# source_eagle.net
KiCad netlist of a schematic drawn in EAGLE
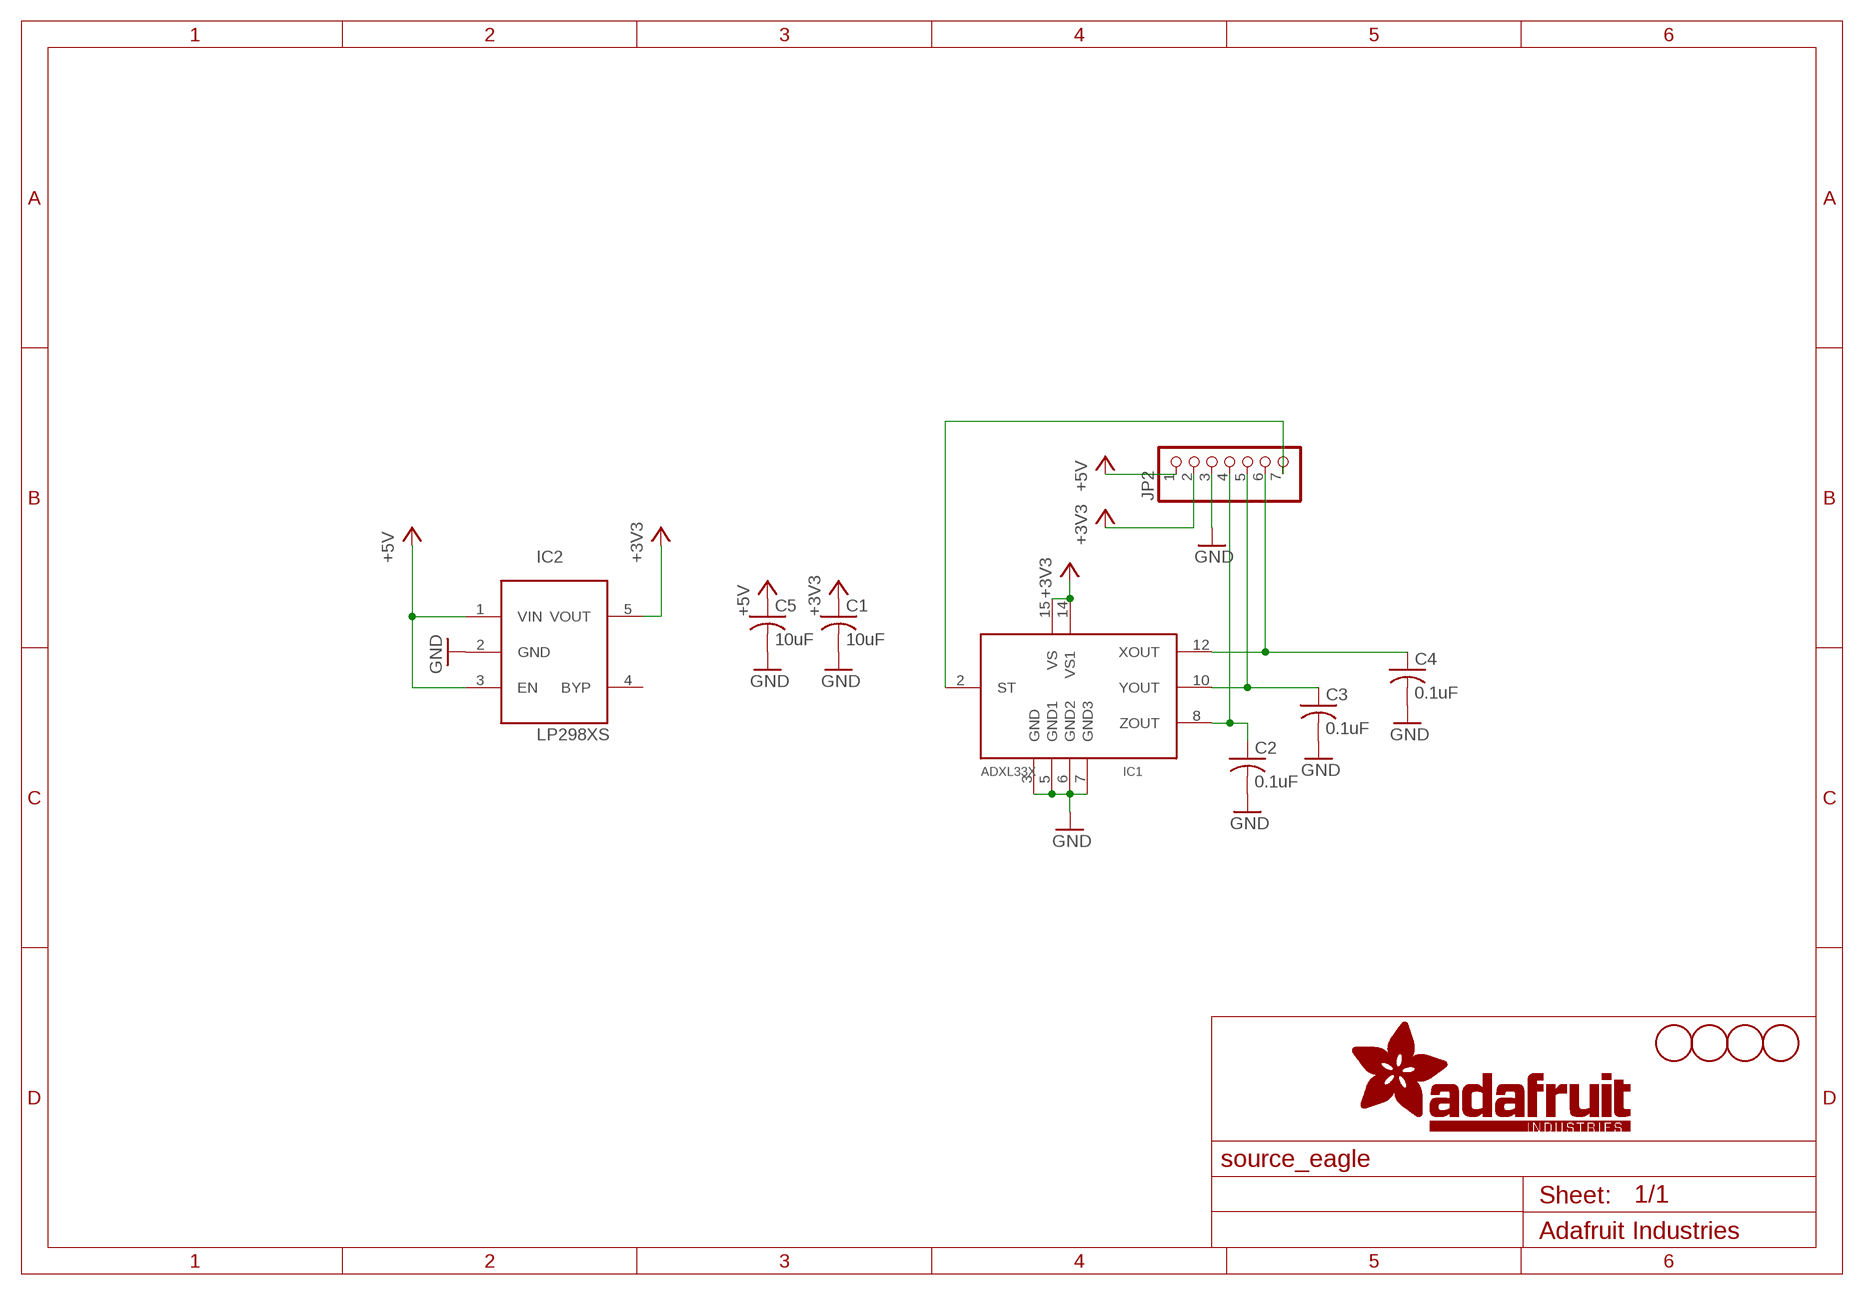
[diagram p0: schematic, sheet 1]

(export (version "E")
  (design (tool "Eeschema 10.0.6"))
  (components
    (comp (ref "C1")
      (value "10uF")
      (footprint "eagle-import:C0805K")
      (libsource (lib "eagle-import") (part "C-USC0805K"))
    )
    (comp (ref "C2")
      (value "0.1uF")
      (footprint "eagle-import:C0805K")
      (libsource (lib "eagle-import") (part "C-USC0805K"))
    )
    (comp (ref "C3")
      (value "0.1uF")
      (footprint "eagle-import:C0805K")
      (libsource (lib "eagle-import") (part "C-USC0805K"))
    )
    (comp (ref "C4")
      (value "0.1uF")
      (footprint "eagle-import:C0805K")
      (libsource (lib "eagle-import") (part "C-USC0805K"))
    )
    (comp (ref "C5")
      (value "10uF")
      (footprint "eagle-import:C0805K")
      (libsource (lib "eagle-import") (part "C-USC0805K"))
    )
    (comp (ref "IC1")
      (value "ADXL33X")
      (footprint "eagle-import:16LCSP")
      (libsource (lib "eagle-import") (part "ADXL33X"))
    )
    (comp (ref "IC2")
      (value "LP298XS")
      (footprint "eagle-import:SOT23-5L")
      (libsource (lib "eagle-import") (part "LP298XS"))
    )
    (comp (ref "JP2")
      (value "HEADER-1X7THICKER")
      (footprint "eagle-import:1X07_ROUND_76")
      (libsource (lib "eagle-import") (part "HEADER-1X7THICKER"))
    )
    (comp (ref "U$1")
      (value "FIDUCIAL")
      (footprint "eagle-import:FIDUCIAL_1MM")
      (libsource (lib "eagle-import") (part "FIDUCIAL"))
    )
    (comp (ref "U$2")
      (value "FIDUCIAL")
      (footprint "eagle-import:FIDUCIAL_1MM")
      (libsource (lib "eagle-import") (part "FIDUCIAL"))
    )
    (comp (ref "U$5")
      (value "MOUNTINGHOLE2.0")
      (footprint "eagle-import:MOUNTINGHOLE_2.0_PLATED")
      (libsource (lib "eagle-import") (part "MOUNTINGHOLE2.0"))
    )
    (comp (ref "U$8")
      (value "MOUNTINGHOLE2.0")
      (footprint "eagle-import:MOUNTINGHOLE_2.0_PLATED")
      (libsource (lib "eagle-import") (part "MOUNTINGHOLE2.0"))
    )
  )
  (nets
    (net (code "1") (name "+3V3") (class "Default")
      (node (ref "C1") (pin "1") (pinfunction "1_1") (pintype "passive"))
      (node (ref "IC1") (pin "14") (pinfunction "VS1_14") (pintype "power_in"))
      (node (ref "IC1") (pin "15") (pinfunction "VS_15") (pintype "power_in"))
      (node (ref "IC2") (pin "5") (pinfunction "VOUT_5") (pintype "bidirectional"))
      (node (ref "JP2") (pin "2") (pinfunction "2_2") (pintype "passive"))
    )
    (net (code "2") (name "+5V") (class "Default")
      (node (ref "C5") (pin "1") (pinfunction "1_1") (pintype "passive"))
      (node (ref "IC2") (pin "1") (pinfunction "VIN_1") (pintype "bidirectional"))
      (node (ref "IC2") (pin "3") (pinfunction "EN_3") (pintype "bidirectional"))
      (node (ref "JP2") (pin "1") (pinfunction "1_1") (pintype "passive"))
    )
    (net (code "3") (name "GND") (class "Default")
      (node (ref "C1") (pin "2") (pinfunction "2_2") (pintype "passive"))
      (node (ref "C2") (pin "2") (pinfunction "2_2") (pintype "passive"))
      (node (ref "C3") (pin "2") (pinfunction "2_2") (pintype "passive"))
      (node (ref "C4") (pin "2") (pinfunction "2_2") (pintype "passive"))
      (node (ref "C5") (pin "2") (pinfunction "2_2") (pintype "passive"))
      (node (ref "IC1") (pin "3") (pinfunction "GND_3") (pintype "power_in"))
      (node (ref "IC1") (pin "5") (pinfunction "GND1_5") (pintype "power_in"))
      (node (ref "IC1") (pin "6") (pinfunction "GND2_6") (pintype "power_in"))
      (node (ref "IC1") (pin "7") (pinfunction "GND3_7") (pintype "power_in"))
      (node (ref "IC2") (pin "2") (pinfunction "GND_2") (pintype "bidirectional"))
      (node (ref "JP2") (pin "3") (pinfunction "3_3") (pintype "passive"))
    )
    (net (code "4") (name "Net-(IC1-ST)") (class "Default")
      (node (ref "IC1") (pin "2") (pinfunction "ST_2") (pintype "input"))
      (node (ref "JP2") (pin "7") (pinfunction "7_7") (pintype "passive"))
    )
    (net (code "5") (name "Net-(IC1-XOUT)") (class "Default")
      (node (ref "C4") (pin "1") (pinfunction "1_1") (pintype "passive"))
      (node (ref "IC1") (pin "12") (pinfunction "XOUT_12") (pintype "output"))
      (node (ref "JP2") (pin "6") (pinfunction "6_6") (pintype "passive"))
    )
    (net (code "6") (name "Net-(IC1-YOUT)") (class "Default")
      (node (ref "C3") (pin "1") (pinfunction "1_1") (pintype "passive"))
      (node (ref "IC1") (pin "10") (pinfunction "YOUT_10") (pintype "output"))
      (node (ref "JP2") (pin "5") (pinfunction "5_5") (pintype "passive"))
    )
    (net (code "7") (name "Net-(IC1-ZOUT)") (class "Default")
      (node (ref "C2") (pin "1") (pinfunction "1_1") (pintype "passive"))
      (node (ref "IC1") (pin "8") (pinfunction "ZOUT_8") (pintype "output"))
      (node (ref "JP2") (pin "4") (pinfunction "4_4") (pintype "passive"))
    )
    (net (code "8") (name "unconnected-(IC2-BYP-Pad4)") (class "Default")
      (node (ref "IC2") (pin "4") (pinfunction "BYP_4") (pintype "bidirectional"))
    )
  )
)
